# Snippet_ATmega32A.net
KiCad netlist of a schematic drawn in Altium Designer
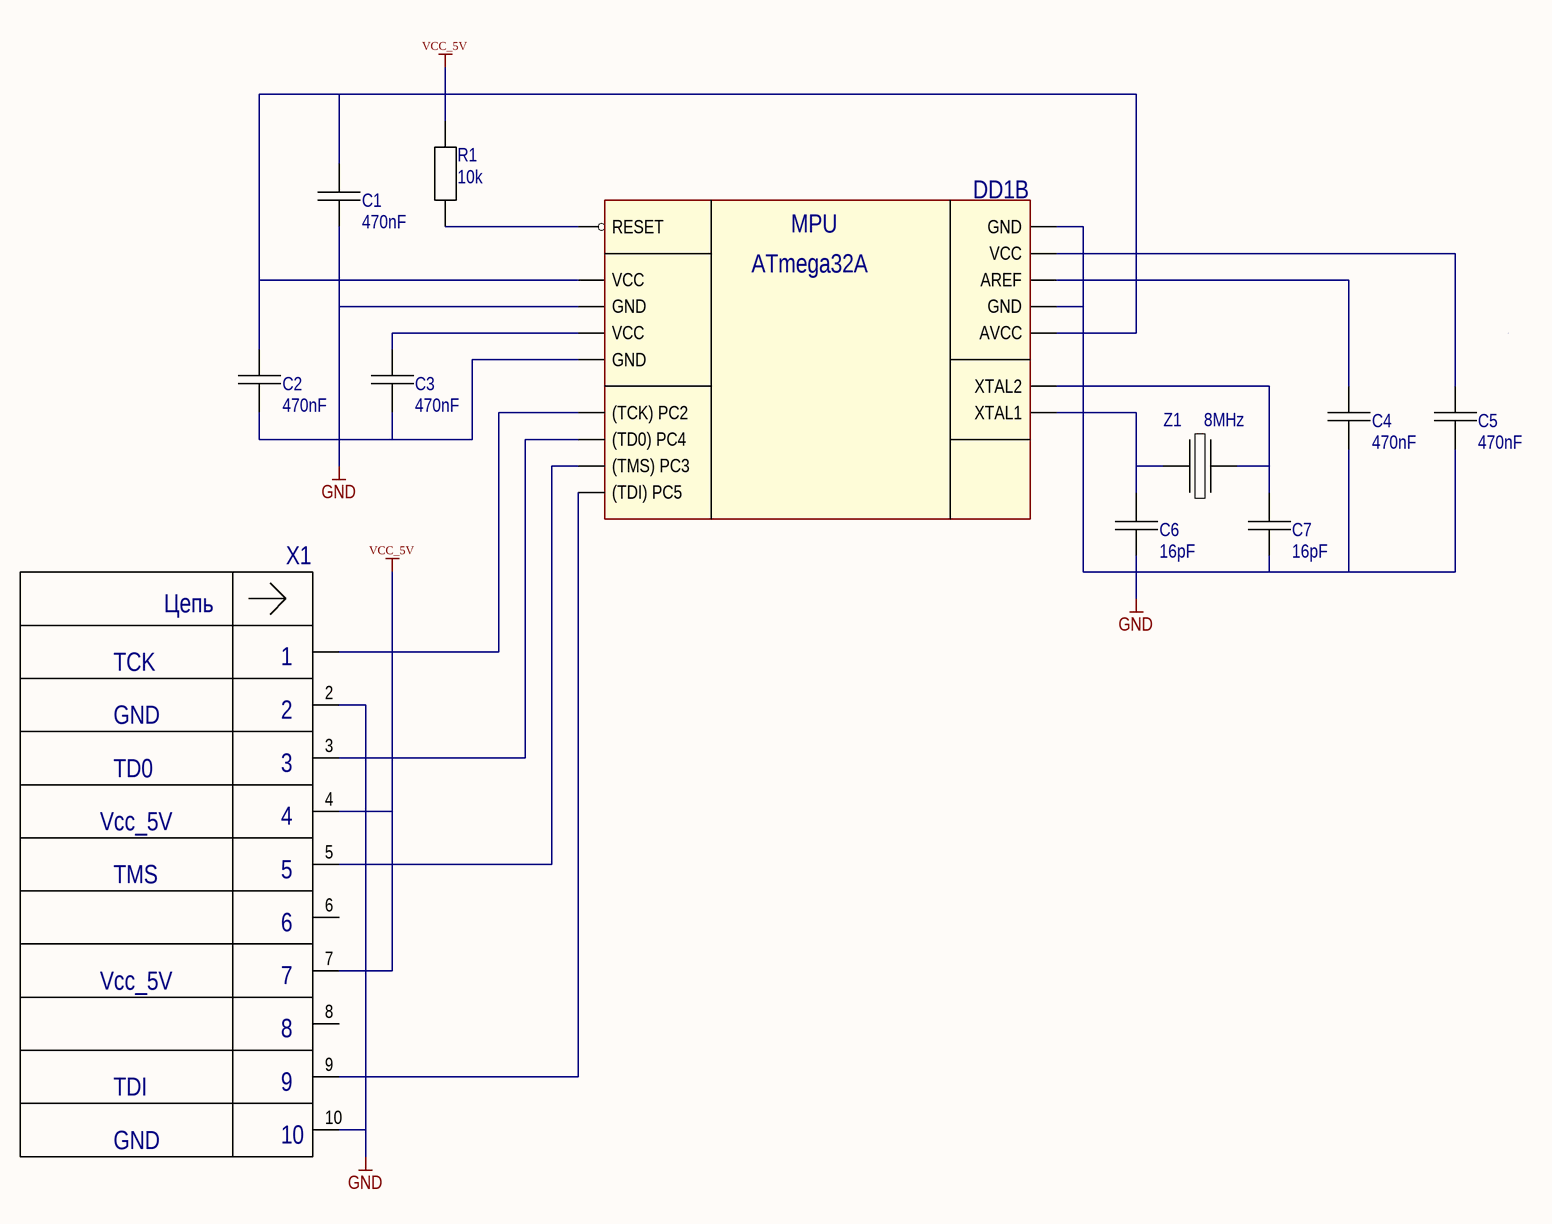
[diagram p0: Snippet_ATmega32A.SchDoc]

(export (version "E")
  (design (tool "Eeschema 10.0.6"))
  (components
    (comp (ref "C1")
      (value "470nF")
      (footprint "Capacitor_0805")
      (libsource (lib "Библиотека элементов") (part "Capacitor_0805"))
    )
    (comp (ref "C2")
      (value "470nF")
      (footprint "Capacitor_0805")
      (libsource (lib "Библиотека элементов") (part "Capacitor_0805"))
    )
    (comp (ref "C3")
      (value "470nF")
      (footprint "Capacitor_0805")
      (libsource (lib "Библиотека элементов") (part "Capacitor_0805"))
    )
    (comp (ref "C4")
      (value "470nF")
      (footprint "Capacitor_0805")
      (libsource (lib "Библиотека элементов") (part "Capacitor_0805"))
    )
    (comp (ref "C5")
      (value "470nF")
      (footprint "Capacitor_0805")
      (libsource (lib "Библиотека элементов") (part "Capacitor_0805"))
    )
    (comp (ref "C6")
      (value "16pF")
      (footprint "Capacitor_0805")
      (libsource (lib "Библиотека элементов") (part "Capacitor_0805"))
    )
    (comp (ref "C7")
      (value "16pF")
      (footprint "Capacitor_0805")
      (libsource (lib "Библиотека элементов") (part "Capacitor_0805"))
    )
    (comp (ref "DD1")
      (value "ATmega32A_TQFP")
      (footprint "ATmega32A_TQFP44")
      (libsource (lib "Библиотека элементов") (part "ATmega32A_TQFP"))
    )
    (comp (ref "R1")
      (value "10k")
      (footprint "RESISTOR_SMD0805")
      (libsource (lib "Библиотека элементов") (part "Resistor_0805"))
    )
    (comp (ref "X1")
      (value "Connector_PLD-10")
      (footprint "CONNECTOR_PLD-10")
      (libsource (lib "Библиотека элементов") (part "Connector_PLD-10"))
    )
    (comp (ref "Z1")
      (value "8MHz")
      (footprint "Quartz_KX-9")
      (libsource (lib "Библиотека элементов") (part "Quartz_KX-9A"))
    )
  )
  (nets
    (net (code "1") (name "GND") (class "Default")
      (node (ref "C1") (pin "2") (pinfunction "2_2") (pintype "passive"))
      (node (ref "C2") (pin "1") (pinfunction "1_1") (pintype "passive"))
      (node (ref "C3") (pin "1") (pinfunction "1_1") (pintype "passive"))
      (node (ref "C4") (pin "1") (pinfunction "1_1") (pintype "passive"))
      (node (ref "C5") (pin "1") (pinfunction "1_1") (pintype "passive"))
      (node (ref "C6") (pin "2") (pinfunction "2_2") (pintype "passive"))
      (node (ref "C7") (pin "2") (pinfunction "2_2") (pintype "passive"))
      (node (ref "DD1") (pin "18") (pinfunction "GND_18") (pintype "power_in"))
      (node (ref "DD1") (pin "28") (pinfunction "GND_28") (pintype "power_in"))
      (node (ref "DD1") (pin "39") (pinfunction "GND_39") (pintype "power_in"))
      (node (ref "DD1") (pin "6") (pinfunction "GND_6") (pintype "power_in"))
      (node (ref "X1") (pin "10") (pinfunction "10_10") (pintype "passive"))
      (node (ref "X1") (pin "2") (pinfunction "2_2") (pintype "passive"))
    )
    (net (code "2") (name "Net-(C3-Pad2)") (class "Default")
      (node (ref "C3") (pin "2") (pinfunction "2_2") (pintype "passive"))
      (node (ref "DD1") (pin "17") (pinfunction "VCC_17") (pintype "power_in"))
    )
    (net (code "3") (name "Net-(DD1B-(TCK)_PC2)") (class "Default")
      (node (ref "DD1") (pin "21") (pinfunction "(TCK)_PC2_21") (pintype "passive"))
      (node (ref "X1") (pin "1") (pinfunction "1_1") (pintype "passive"))
    )
    (net (code "4") (name "Net-(DD1B-(TD0)_PC4)") (class "Default")
      (node (ref "DD1") (pin "23") (pinfunction "(TD0)_PC4_23") (pintype "passive"))
      (node (ref "X1") (pin "3") (pinfunction "3_3") (pintype "passive"))
    )
    (net (code "5") (name "Net-(DD1B-(TDI)_PC5)") (class "Default")
      (node (ref "DD1") (pin "24") (pinfunction "(TDI)_PC5_24") (pintype "passive"))
      (node (ref "X1") (pin "9") (pinfunction "9_9") (pintype "passive"))
    )
    (net (code "6") (name "Net-(DD1B-(TMS)_PC3)") (class "Default")
      (node (ref "DD1") (pin "22") (pinfunction "(TMS)_PC3_22") (pintype "passive"))
      (node (ref "X1") (pin "5") (pinfunction "5_5") (pintype "passive"))
    )
    (net (code "7") (name "Net-(DD1B-RESET)") (class "Default")
      (node (ref "DD1") (pin "4") (pinfunction "RESET_4") (pintype "passive"))
      (node (ref "R1") (pin "1") (pinfunction "1_1") (pintype "passive"))
    )
    (net (code "8") (name "Net-(DD1B-XTAL1)") (class "Default")
      (node (ref "C6") (pin "1") (pinfunction "1_1") (pintype "passive"))
      (node (ref "DD1") (pin "8") (pinfunction "XTAL1_8") (pintype "passive"))
      (node (ref "Z1") (pin "1") (pinfunction "1_1") (pintype "passive"))
    )
    (net (code "9") (name "Net-(DD1B-XTAL2)") (class "Default")
      (node (ref "C7") (pin "1") (pinfunction "1_1") (pintype "passive"))
      (node (ref "DD1") (pin "7") (pinfunction "XTAL2_7") (pintype "passive"))
      (node (ref "Z1") (pin "3") (pinfunction "3_3") (pintype "passive"))
    )
    (net (code "10") (name "VCC_5V") (class "Default")
      (node (ref "C1") (pin "1") (pinfunction "1_1") (pintype "passive"))
      (node (ref "C2") (pin "2") (pinfunction "2_2") (pintype "passive"))
      (node (ref "C4") (pin "2") (pinfunction "2_2") (pintype "passive"))
      (node (ref "C5") (pin "2") (pinfunction "2_2") (pintype "passive"))
      (node (ref "DD1") (pin "27") (pinfunction "AVCC_27") (pintype "power_in"))
      (node (ref "DD1") (pin "29") (pinfunction "AREF_29") (pintype "passive"))
      (node (ref "DD1") (pin "38") (pinfunction "VCC_38") (pintype "power_in"))
      (node (ref "DD1") (pin "5") (pinfunction "VCC_5") (pintype "power_in"))
      (node (ref "R1") (pin "2") (pinfunction "2_2") (pintype "passive"))
      (node (ref "X1") (pin "4") (pinfunction "4_4") (pintype "passive"))
      (node (ref "X1") (pin "7") (pinfunction "7_7") (pintype "passive"))
    )
    (net (code "11") (name "unconnected-(X1-Pad6)") (class "Default")
      (node (ref "X1") (pin "6") (pinfunction "6_6") (pintype "passive"))
    )
    (net (code "12") (name "unconnected-(X1-Pad8)") (class "Default")
      (node (ref "X1") (pin "8") (pinfunction "8_8") (pintype "passive"))
    )
  )
)
